# Sheet1.net
KiCad netlist of a schematic drawn in Altium Designer
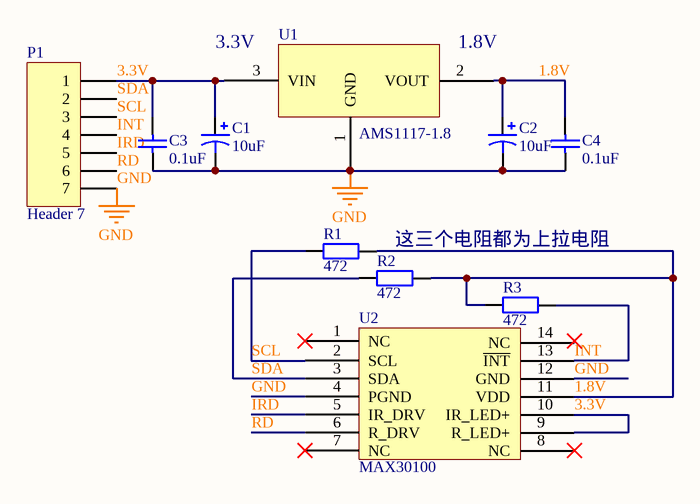
[diagram p0: Sheet1.SchDoc]

(export (version "E")
  (design (tool "Eeschema 10.0.6"))
  (components
    (comp (ref "C1")
      (value "10uF")
      (footprint "1210")
      (description "Polarized Capacitor (Radial)")
      (fields (field (name "Comment") "Cap Pol1") (field (name "PUBLISHER") "Altium Limited"))
      (libsource (lib "Miscellaneous Devices") (part "Cap Pol1"))
    )
    (comp (ref "C2")
      (value "10uF")
      (footprint "1210")
      (description "Polarized Capacitor (Radial)")
      (fields (field (name "Comment") "Cap Pol1") (field (name "PUBLISHER") "Altium Limited"))
      (libsource (lib "Miscellaneous Devices") (part "Cap Pol1"))
    )
    (comp (ref "C3")
      (value "0.1uF")
      (footprint "0603")
      (description "Capacitor")
      (fields (field (name "Comment") "Cap") (field (name "PUBLISHER") "Altium Limited"))
      (libsource (lib "Miscellaneous Devices") (part "Cap"))
    )
    (comp (ref "C4")
      (value "0.1uF")
      (footprint "0603")
      (description "Capacitor")
      (fields (field (name "Comment") "Cap") (field (name "PUBLISHER") "Altium Limited"))
      (libsource (lib "Miscellaneous Devices") (part "Cap"))
    )
    (comp (ref "P1")
      (value "Header 7")
      (footprint "HDR1X7")
      (description "Header, 7-Pin")
      (fields (field (name "PUBLISHER") "Altium Limited"))
      (libsource (lib "Miscellaneous Connectors") (part "Header 7"))
    )
    (comp (ref "R1")
      (value "472")
      (footprint "0603")
      (description "Resistor")
      (fields (field (name "Comment") "Res2") (field (name "PUBLISHER") "Altium Limited"))
      (libsource (lib "Miscellaneous Devices") (part "Res2"))
    )
    (comp (ref "R2")
      (value "472")
      (footprint "0603")
      (description "Resistor")
      (fields (field (name "Comment") "Res2") (field (name "PUBLISHER") "Altium Limited"))
      (libsource (lib "Miscellaneous Devices") (part "Res2"))
    )
    (comp (ref "R3")
      (value "472")
      (footprint "0603")
      (description "Resistor")
      (fields (field (name "Comment") "Res2") (field (name "PUBLISHER") "Altium Limited"))
      (libsource (lib "Miscellaneous Devices") (part "Res2"))
    )
    (comp (ref "U1")
      (value "AMS1117-1.8")
      (footprint "SOT-223")
      (description "3.3V~12V->1.8V")
      (libsource (lib "Schlib1") (part "AMS1117-1.8"))
    )
    (comp (ref "U2") (value "MAX30100") (footprint "MAX30100") (libsource (lib "Schlib1") (part "MAX30100")))
  )
  (nets
    (net (code "1") (name "/1.8V") (class "Default")
      (node (ref "C2") (pin "1") (pinfunction "1_1") (pintype "passive"))
      (node (ref "C4") (pin "2") (pinfunction "2_2") (pintype "passive"))
      (node (ref "R1") (pin "2") (pinfunction "2_2") (pintype "passive"))
      (node (ref "R2") (pin "2") (pinfunction "2_2") (pintype "passive"))
      (node (ref "R3") (pin "1") (pinfunction "1_1") (pintype "passive"))
      (node (ref "U1") (pin "2") (pinfunction "VOUT_2") (pintype "power_in"))
      (node (ref "U2") (pin "11") (pinfunction "VDD_11") (pintype "passive"))
    )
    (net (code "2") (name "/3.3V") (class "Default")
      (node (ref "C1") (pin "1") (pinfunction "1_1") (pintype "passive"))
      (node (ref "C3") (pin "1") (pinfunction "1_1") (pintype "passive"))
      (node (ref "P1") (pin "1") (pinfunction "1_1") (pintype "passive"))
      (node (ref "U1") (pin "3") (pinfunction "VIN_3") (pintype "power_in"))
      (node (ref "U2") (pin "10") (pinfunction "IR_LED+_10") (pintype "passive"))
      (node (ref "U2") (pin "9") (pinfunction "R_LED+_9") (pintype "passive"))
    )
    (net (code "3") (name "/INT") (class "Default")
      (node (ref "P1") (pin "4") (pinfunction "4_4") (pintype "passive"))
      (node (ref "R3") (pin "2") (pinfunction "2_2") (pintype "passive"))
      (node (ref "U2") (pin "13") (pinfunction "~{INT}_13") (pintype "passive"))
    )
    (net (code "4") (name "/IRD") (class "Default")
      (node (ref "P1") (pin "5") (pinfunction "5_5") (pintype "passive"))
      (node (ref "U2") (pin "5") (pinfunction "IR_DRV_5") (pintype "passive"))
    )
    (net (code "5") (name "/RD") (class "Default")
      (node (ref "P1") (pin "6") (pinfunction "6_6") (pintype "passive"))
      (node (ref "U2") (pin "6") (pinfunction "R_DRV_6") (pintype "passive"))
    )
    (net (code "6") (name "/SCL") (class "Default")
      (node (ref "P1") (pin "3") (pinfunction "3_3") (pintype "passive"))
      (node (ref "R1") (pin "1") (pinfunction "1_1") (pintype "passive"))
      (node (ref "U2") (pin "2") (pinfunction "SCL_2") (pintype "passive"))
    )
    (net (code "7") (name "/SDA") (class "Default")
      (node (ref "P1") (pin "2") (pinfunction "2_2") (pintype "passive"))
      (node (ref "R2") (pin "1") (pinfunction "1_1") (pintype "passive"))
      (node (ref "U2") (pin "3") (pinfunction "SDA_3") (pintype "passive"))
    )
    (net (code "8") (name "GND") (class "Default")
      (node (ref "C1") (pin "2") (pinfunction "2_2") (pintype "passive"))
      (node (ref "C2") (pin "2") (pinfunction "2_2") (pintype "passive"))
      (node (ref "C3") (pin "2") (pinfunction "2_2") (pintype "passive"))
      (node (ref "C4") (pin "1") (pinfunction "1_1") (pintype "passive"))
      (node (ref "P1") (pin "7") (pinfunction "7_7") (pintype "passive"))
      (node (ref "U1") (pin "1") (pinfunction "GND_1") (pintype "power_in"))
      (node (ref "U2") (pin "12") (pinfunction "GND_12") (pintype "passive"))
      (node (ref "U2") (pin "4") (pinfunction "PGND_4") (pintype "passive"))
    )
    (net (code "9") (name "unconnected-(U2-NC-Pad1)") (class "Default")
      (node (ref "U2") (pin "1") (pinfunction "NC_1") (pintype "passive+no_connect"))
    )
    (net (code "10") (name "unconnected-(U2-NC-Pad7)") (class "Default")
      (node (ref "U2") (pin "7") (pinfunction "NC_7") (pintype "passive+no_connect"))
    )
    (net (code "11") (name "unconnected-(U2-NC-Pad8)") (class "Default")
      (node (ref "U2") (pin "8") (pinfunction "NC_8") (pintype "passive+no_connect"))
    )
    (net (code "12") (name "unconnected-(U2-NC-Pad14)") (class "Default")
      (node (ref "U2") (pin "14") (pinfunction "NC_14") (pintype "passive"))
    )
  )
)
